# CON_HOSTJTAG_10WBOXHDRRAM.net
KiCad netlist of a schematic drawn in Altium Designer
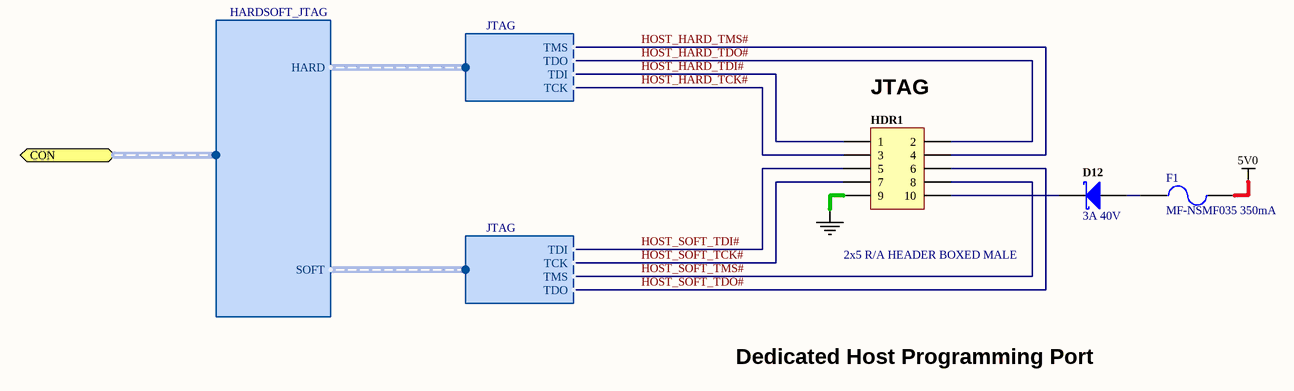
[diagram p0: CON_HOSTJTAG_10WBOXHDRRAM.SchDoc]

(export (version "E")
  (design (tool "Eeschema 10.0.6"))
  (components
    (comp (ref "D12")
      (value "3A 40V")
      (footprint "DIOM5027")
      (description "Schottky Diode, 3A 40V")
      (libsource (lib "altium-import") (part "root_2_DIO-SCHOTTKY-1S_"))
    )
    (comp (ref "F1")
      (value "MF-NSMF035 350mA")
      (footprint "RESC3216")
      (description "Multifuse, SMD 1206, 350mA")
      (libsource (lib "AltiumDesignLibrary") (part "MULTIFUSE"))
    )
    (comp (ref "HDR1")
      (value "2x5 R/A HEADER BOXED MALE")
      (footprint "918510x323")
      (description "Header IDC, 2 x 5 Pin Right-Angle 2.54mm Pitch (Boxed-Male)")
      (libsource (lib "altium-import") (part "root_0_CON-IDC-2x5-M-RA_"))
    )
  )
  (nets
    (net (code "4") (name "/HOST_HARD_TCK#") (class "Default")
      (node (ref "HDR1") (pin "3") (pinfunction "3_3") (pintype "passive"))
    )
    (net (code "5") (name "/HOST_HARD_TDI#") (class "Default")
      (node (ref "HDR1") (pin "1") (pinfunction "1_1") (pintype "passive"))
    )
    (net (code "6") (name "/HOST_HARD_TDO#") (class "Default")
      (node (ref "HDR1") (pin "2") (pinfunction "2_2") (pintype "passive"))
    )
    (net (code "7") (name "/HOST_HARD_TMS#") (class "Default")
      (node (ref "HDR1") (pin "4") (pinfunction "4_4") (pintype "passive"))
    )
    (net (code "8") (name "/HOST_SOFT_TCK#") (class "Default")
      (node (ref "HDR1") (pin "7") (pinfunction "7_7") (pintype "passive"))
    )
    (net (code "9") (name "/HOST_SOFT_TDI#") (class "Default")
      (node (ref "HDR1") (pin "5") (pinfunction "5_5") (pintype "passive"))
    )
    (net (code "10") (name "/HOST_SOFT_TDO#") (class "Default")
      (node (ref "HDR1") (pin "6") (pinfunction "6_6") (pintype "passive"))
    )
    (net (code "11") (name "/HOST_SOFT_TMS#") (class "Default")
      (node (ref "HDR1") (pin "8") (pinfunction "8_8") (pintype "passive"))
    )
    (net (code "13") (name "5V0") (class "Default")
      (node (ref "F1") (pin "2") (pinfunction "2_2") (pintype "passive"))
    )
    (net (code "14") (name "GND") (class "Default")
      (node (ref "HDR1") (pin "9") (pinfunction "9_9") (pintype "passive"))
    )
    (net (code "15") (name "Net-(D12-A)") (class "Default")
      (node (ref "D12") (pin "1") (pinfunction "A_1") (pintype "passive"))
      (node (ref "F1") (pin "1") (pinfunction "1_1") (pintype "passive"))
    )
    (net (code "16") (name "Net-(D12-K)") (class "Default")
      (node (ref "D12") (pin "2") (pinfunction "K_2") (pintype "passive"))
      (node (ref "HDR1") (pin "10") (pinfunction "10_10") (pintype "passive"))
    )
  )
)
